# LissajousRevA.net
KiCad netlist of a schematic drawn in EAGLE
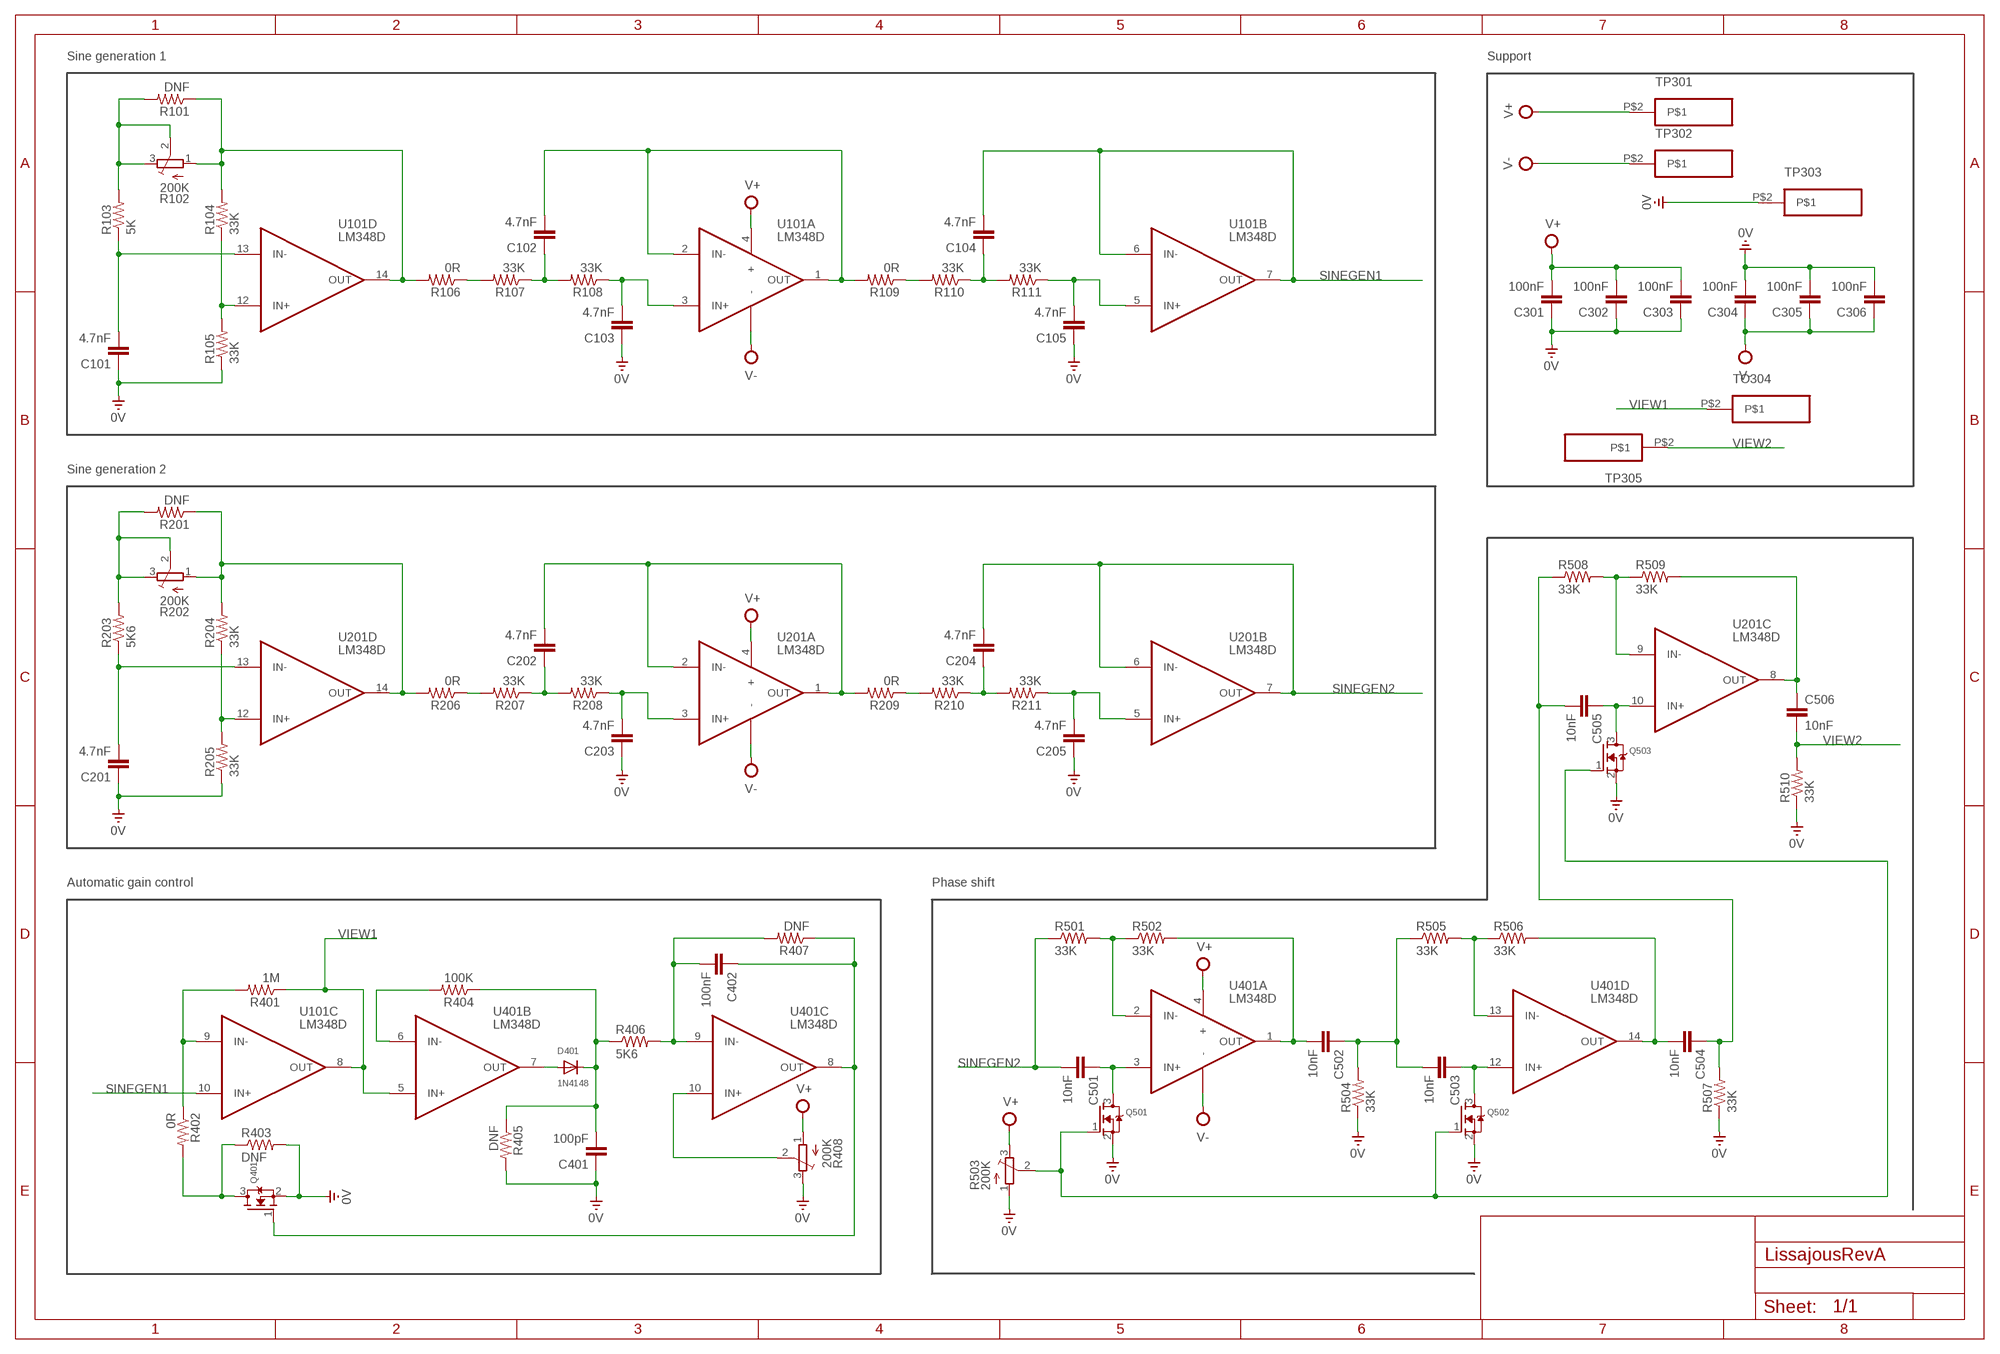
[diagram p0: schematic, sheet 1]

(export (version "E")
  (design (tool "Eeschema 10.0.6"))
  (components
    (comp (ref "C101")
      (value "4.7nF")
      (footprint "eagle-import:0603-CAP")
      (libsource (lib "eagle-import") (part "CAP0603-CAP"))
    )
    (comp (ref "C102")
      (value "4.7nF")
      (footprint "eagle-import:0603-CAP")
      (libsource (lib "eagle-import") (part "CAP0603-CAP"))
    )
    (comp (ref "C103")
      (value "4.7nF")
      (footprint "eagle-import:0603-CAP")
      (libsource (lib "eagle-import") (part "CAP0603-CAP"))
    )
    (comp (ref "C104")
      (value "4.7nF")
      (footprint "eagle-import:0603-CAP")
      (libsource (lib "eagle-import") (part "CAP0603-CAP"))
    )
    (comp (ref "C105")
      (value "4.7nF")
      (footprint "eagle-import:0603-CAP")
      (libsource (lib "eagle-import") (part "CAP0603-CAP"))
    )
    (comp (ref "C201")
      (value "4.7nF")
      (footprint "eagle-import:0603-CAP")
      (libsource (lib "eagle-import") (part "CAP0603-CAP"))
    )
    (comp (ref "C202")
      (value "4.7nF")
      (footprint "eagle-import:0603-CAP")
      (libsource (lib "eagle-import") (part "CAP0603-CAP"))
    )
    (comp (ref "C203")
      (value "4.7nF")
      (footprint "eagle-import:0603-CAP")
      (libsource (lib "eagle-import") (part "CAP0603-CAP"))
    )
    (comp (ref "C204")
      (value "4.7nF")
      (footprint "eagle-import:0603-CAP")
      (libsource (lib "eagle-import") (part "CAP0603-CAP"))
    )
    (comp (ref "C205")
      (value "4.7nF")
      (footprint "eagle-import:0603-CAP")
      (libsource (lib "eagle-import") (part "CAP0603-CAP"))
    )
    (comp (ref "C301")
      (value "100nF")
      (footprint "eagle-import:0603-CAP")
      (libsource (lib "eagle-import") (part "CAP0603-CAP"))
    )
    (comp (ref "C302")
      (value "100nF")
      (footprint "eagle-import:0603-CAP")
      (libsource (lib "eagle-import") (part "CAP0603-CAP"))
    )
    (comp (ref "C303")
      (value "100nF")
      (footprint "eagle-import:0603-CAP")
      (libsource (lib "eagle-import") (part "CAP0603-CAP"))
    )
    (comp (ref "C304")
      (value "100nF")
      (footprint "eagle-import:0603-CAP")
      (libsource (lib "eagle-import") (part "CAP0603-CAP"))
    )
    (comp (ref "C305")
      (value "100nF")
      (footprint "eagle-import:0603-CAP")
      (libsource (lib "eagle-import") (part "CAP0603-CAP"))
    )
    (comp (ref "C306")
      (value "100nF")
      (footprint "eagle-import:0603-CAP")
      (libsource (lib "eagle-import") (part "CAP0603-CAP"))
    )
    (comp (ref "C401")
      (value "100pF")
      (footprint "eagle-import:0603-CAP")
      (libsource (lib "eagle-import") (part "CAP0603-CAP"))
    )
    (comp (ref "C402")
      (value "100nF")
      (footprint "eagle-import:0603-CAP")
      (libsource (lib "eagle-import") (part "CAP0603-CAP"))
    )
    (comp (ref "C501")
      (value "10nF")
      (footprint "eagle-import:0603-CAP")
      (libsource (lib "eagle-import") (part "CAP0603-CAP"))
    )
    (comp (ref "C502")
      (value "10nF")
      (footprint "eagle-import:0603-CAP")
      (libsource (lib "eagle-import") (part "CAP0603-CAP"))
    )
    (comp (ref "C503")
      (value "10nF")
      (footprint "eagle-import:0603-CAP")
      (libsource (lib "eagle-import") (part "CAP0603-CAP"))
    )
    (comp (ref "C504")
      (value "10nF")
      (footprint "eagle-import:0603-CAP")
      (libsource (lib "eagle-import") (part "CAP0603-CAP"))
    )
    (comp (ref "C505")
      (value "10nF")
      (footprint "eagle-import:0603-CAP")
      (libsource (lib "eagle-import") (part "CAP0603-CAP"))
    )
    (comp (ref "C506")
      (value "10nF")
      (footprint "eagle-import:0603-CAP")
      (libsource (lib "eagle-import") (part "CAP0603-CAP"))
    )
    (comp (ref "D401")
      (value "1N4148")
      (footprint "eagle-import:SMADIODE")
      (libsource (lib "eagle-import") (part "DIODESMA"))
    )
    (comp (ref "Q401")
      (value "MOSFET-NREFLOW")
      (footprint "eagle-import:SOT23")
      (libsource (lib "eagle-import") (part "MOSFET-NREFLOW"))
    )
    (comp (ref "Q501")
      (value "MOSFET-NREFLOW")
      (footprint "eagle-import:SOT23")
      (libsource (lib "eagle-import") (part "MOSFET-NREFLOW"))
    )
    (comp (ref "Q502")
      (value "MOSFET-NREFLOW")
      (footprint "eagle-import:SOT23")
      (libsource (lib "eagle-import") (part "MOSFET-NREFLOW"))
    )
    (comp (ref "Q503")
      (value "MOSFET-NREFLOW")
      (footprint "eagle-import:SOT23")
      (libsource (lib "eagle-import") (part "MOSFET-NREFLOW"))
    )
    (comp (ref "R101")
      (value "DNF")
      (footprint "eagle-import:0603-RES")
      (libsource (lib "eagle-import") (part "RESISTOR0603-RES"))
    )
    (comp (ref "R102")
      (value "200K")
      (footprint "eagle-import:TC33X")
      (libsource (lib "eagle-import") (part "TRIMPOTTC33X"))
    )
    (comp (ref "R103")
      (value "5K")
      (footprint "eagle-import:0603-RES")
      (libsource (lib "eagle-import") (part "RESISTOR0603-RES"))
    )
    (comp (ref "R104")
      (value "33K")
      (footprint "eagle-import:0603-RES")
      (libsource (lib "eagle-import") (part "RESISTOR0603-RES"))
    )
    (comp (ref "R105")
      (value "33K")
      (footprint "eagle-import:0603-RES")
      (libsource (lib "eagle-import") (part "RESISTOR0603-RES"))
    )
    (comp (ref "R106")
      (value "0R")
      (footprint "eagle-import:0603-RES")
      (libsource (lib "eagle-import") (part "RESISTOR0603-RES"))
    )
    (comp (ref "R107")
      (value "33K")
      (footprint "eagle-import:0603-RES")
      (libsource (lib "eagle-import") (part "RESISTOR0603-RES"))
    )
    (comp (ref "R108")
      (value "33K")
      (footprint "eagle-import:0603-RES")
      (libsource (lib "eagle-import") (part "RESISTOR0603-RES"))
    )
    (comp (ref "R109")
      (value "0R")
      (footprint "eagle-import:0603-RES")
      (libsource (lib "eagle-import") (part "RESISTOR0603-RES"))
    )
    (comp (ref "R110")
      (value "33K")
      (footprint "eagle-import:0603-RES")
      (libsource (lib "eagle-import") (part "RESISTOR0603-RES"))
    )
    (comp (ref "R111")
      (value "33K")
      (footprint "eagle-import:0603-RES")
      (libsource (lib "eagle-import") (part "RESISTOR0603-RES"))
    )
    (comp (ref "R201")
      (value "DNF")
      (footprint "eagle-import:0603-RES")
      (libsource (lib "eagle-import") (part "RESISTOR0603-RES"))
    )
    (comp (ref "R202")
      (value "200K")
      (footprint "eagle-import:TC33X")
      (libsource (lib "eagle-import") (part "TRIMPOTTC33X"))
    )
    (comp (ref "R203")
      (value "5K6")
      (footprint "eagle-import:0603-RES")
      (libsource (lib "eagle-import") (part "RESISTOR0603-RES"))
    )
    (comp (ref "R204")
      (value "33K")
      (footprint "eagle-import:0603-RES")
      (libsource (lib "eagle-import") (part "RESISTOR0603-RES"))
    )
    (comp (ref "R205")
      (value "33K")
      (footprint "eagle-import:0603-RES")
      (libsource (lib "eagle-import") (part "RESISTOR0603-RES"))
    )
    (comp (ref "R206")
      (value "0R")
      (footprint "eagle-import:0603-RES")
      (libsource (lib "eagle-import") (part "RESISTOR0603-RES"))
    )
    (comp (ref "R207")
      (value "33K")
      (footprint "eagle-import:0603-RES")
      (libsource (lib "eagle-import") (part "RESISTOR0603-RES"))
    )
    (comp (ref "R208")
      (value "33K")
      (footprint "eagle-import:0603-RES")
      (libsource (lib "eagle-import") (part "RESISTOR0603-RES"))
    )
    (comp (ref "R209")
      (value "0R")
      (footprint "eagle-import:0603-RES")
      (libsource (lib "eagle-import") (part "RESISTOR0603-RES"))
    )
    (comp (ref "R210")
      (value "33K")
      (footprint "eagle-import:0603-RES")
      (libsource (lib "eagle-import") (part "RESISTOR0603-RES"))
    )
    (comp (ref "R211")
      (value "33K")
      (footprint "eagle-import:0603-RES")
      (libsource (lib "eagle-import") (part "RESISTOR0603-RES"))
    )
    (comp (ref "R401")
      (value "1M")
      (footprint "eagle-import:0603-RES")
      (libsource (lib "eagle-import") (part "RESISTOR0603-RES"))
    )
    (comp (ref "R402")
      (value "0R")
      (footprint "eagle-import:0603-RES")
      (libsource (lib "eagle-import") (part "RESISTOR0603-RES"))
    )
    (comp (ref "R403")
      (value "DNF")
      (footprint "eagle-import:0603-RES")
      (libsource (lib "eagle-import") (part "RESISTOR0603-RES"))
    )
    (comp (ref "R404")
      (value "100K")
      (footprint "eagle-import:0603-RES")
      (libsource (lib "eagle-import") (part "RESISTOR0603-RES"))
    )
    (comp (ref "R405")
      (value "DNF")
      (footprint "eagle-import:0603-RES")
      (libsource (lib "eagle-import") (part "RESISTOR0603-RES"))
    )
    (comp (ref "R406")
      (value "5K6")
      (footprint "eagle-import:0603-RES")
      (libsource (lib "eagle-import") (part "RESISTOR0603-RES"))
    )
    (comp (ref "R407")
      (value "DNF")
      (footprint "eagle-import:0603-RES")
      (libsource (lib "eagle-import") (part "RESISTOR0603-RES"))
    )
    (comp (ref "R408")
      (value "200K")
      (footprint "eagle-import:TC33X")
      (libsource (lib "eagle-import") (part "TRIMPOTTC33X"))
    )
    (comp (ref "R501")
      (value "33K")
      (footprint "eagle-import:0603-RES")
      (libsource (lib "eagle-import") (part "RESISTOR0603-RES"))
    )
    (comp (ref "R502")
      (value "33K")
      (footprint "eagle-import:0603-RES")
      (libsource (lib "eagle-import") (part "RESISTOR0603-RES"))
    )
    (comp (ref "R503")
      (value "200K")
      (footprint "eagle-import:TC33X")
      (libsource (lib "eagle-import") (part "TRIMPOTTC33X"))
    )
    (comp (ref "R504")
      (value "33K")
      (footprint "eagle-import:0603-RES")
      (libsource (lib "eagle-import") (part "RESISTOR0603-RES"))
    )
    (comp (ref "R505")
      (value "33K")
      (footprint "eagle-import:0603-RES")
      (libsource (lib "eagle-import") (part "RESISTOR0603-RES"))
    )
    (comp (ref "R506")
      (value "33K")
      (footprint "eagle-import:0603-RES")
      (libsource (lib "eagle-import") (part "RESISTOR0603-RES"))
    )
    (comp (ref "R507")
      (value "33K")
      (footprint "eagle-import:0603-RES")
      (libsource (lib "eagle-import") (part "RESISTOR0603-RES"))
    )
    (comp (ref "R508")
      (value "33K")
      (footprint "eagle-import:0603-RES")
      (libsource (lib "eagle-import") (part "RESISTOR0603-RES"))
    )
    (comp (ref "R509")
      (value "33K")
      (footprint "eagle-import:0603-RES")
      (libsource (lib "eagle-import") (part "RESISTOR0603-RES"))
    )
    (comp (ref "R510")
      (value "33K")
      (footprint "eagle-import:0603-RES")
      (libsource (lib "eagle-import") (part "RESISTOR0603-RES"))
    )
    (comp (ref "TO304")
      (value "PAD")
      (footprint "eagle-import:PAD")
      (libsource (lib "eagle-import") (part "PAD"))
    )
    (comp (ref "TP301")
      (value "PAD")
      (footprint "eagle-import:PAD")
      (libsource (lib "eagle-import") (part "PAD"))
    )
    (comp (ref "TP302")
      (value "PAD")
      (footprint "eagle-import:PAD")
      (libsource (lib "eagle-import") (part "PAD"))
    )
    (comp (ref "TP303")
      (value "PAD")
      (footprint "eagle-import:PAD")
      (libsource (lib "eagle-import") (part "PAD"))
    )
    (comp (ref "TP305")
      (value "PAD")
      (footprint "eagle-import:PAD")
      (libsource (lib "eagle-import") (part "PAD"))
    )
    (comp (ref "U101")
      (value "LM348D")
      (footprint "eagle-import:SOIC127P600X175-14N")
      (libsource (lib "eagle-import") (part "LM348D"))
    )
    (comp (ref "U201")
      (value "LM348D")
      (footprint "eagle-import:SOIC127P600X175-14N")
      (libsource (lib "eagle-import") (part "LM348D"))
    )
    (comp (ref "U401")
      (value "LM348D")
      (footprint "eagle-import:SOIC127P600X175-14N")
      (libsource (lib "eagle-import") (part "LM348D"))
    )
  )
  (nets
    (net (code "1") (name "/SINEGEN1") (class "Default")
      (node (ref "C104") (pin "2") (pinfunction "2_2") (pintype "passive"))
      (node (ref "U101") (pin "10") (pinfunction "IN+_10") (pintype "output"))
      (node (ref "U101") (pin "6") (pinfunction "IN-_6") (pintype "output"))
      (node (ref "U101") (pin "7") (pinfunction "OUT_7") (pintype "output"))
    )
    (net (code "2") (name "/SINEGEN2") (class "Default")
      (node (ref "C204") (pin "2") (pinfunction "2_2") (pintype "passive"))
      (node (ref "C501") (pin "2") (pinfunction "2_2") (pintype "passive"))
      (node (ref "R501") (pin "1") (pinfunction "1_1") (pintype "passive"))
      (node (ref "U201") (pin "6") (pinfunction "IN-_6") (pintype "output"))
      (node (ref "U201") (pin "7") (pinfunction "OUT_7") (pintype "output"))
    )
    (net (code "3") (name "/VIEW1") (class "Default")
      (node (ref "R401") (pin "1") (pinfunction "1_1") (pintype "passive"))
      (node (ref "TO304") (pin "P$2") (pinfunction "P$1_P$2") (pintype "bidirectional"))
      (node (ref "U101") (pin "8") (pinfunction "OUT_8") (pintype "output"))
      (node (ref "U401") (pin "5") (pinfunction "IN+_5") (pintype "output"))
    )
    (net (code "4") (name "/VIEW2") (class "Default")
      (node (ref "C506") (pin "2") (pinfunction "2_2") (pintype "passive"))
      (node (ref "R510") (pin "2") (pinfunction "2_2") (pintype "passive"))
      (node (ref "TP305") (pin "P$2") (pinfunction "P$1_P$2") (pintype "bidirectional"))
    )
    (net (code "5") (name "0V") (class "Default")
      (node (ref "C101") (pin "1") (pinfunction "1_1") (pintype "passive"))
      (node (ref "C103") (pin "1") (pinfunction "1_1") (pintype "passive"))
      (node (ref "C105") (pin "1") (pinfunction "1_1") (pintype "passive"))
      (node (ref "C201") (pin "1") (pinfunction "1_1") (pintype "passive"))
      (node (ref "C203") (pin "1") (pinfunction "1_1") (pintype "passive"))
      (node (ref "C205") (pin "1") (pinfunction "1_1") (pintype "passive"))
      (node (ref "C301") (pin "1") (pinfunction "1_1") (pintype "passive"))
      (node (ref "C302") (pin "1") (pinfunction "1_1") (pintype "passive"))
      (node (ref "C303") (pin "1") (pinfunction "1_1") (pintype "passive"))
      (node (ref "C304") (pin "2") (pinfunction "2_2") (pintype "passive"))
      (node (ref "C305") (pin "2") (pinfunction "2_2") (pintype "passive"))
      (node (ref "C306") (pin "2") (pinfunction "2_2") (pintype "passive"))
      (node (ref "C401") (pin "1") (pinfunction "1_1") (pintype "passive"))
      (node (ref "Q401") (pin "2") (pinfunction "S_2") (pintype "bidirectional"))
      (node (ref "Q501") (pin "2") (pinfunction "S_2") (pintype "bidirectional"))
      (node (ref "Q502") (pin "2") (pinfunction "S_2") (pintype "bidirectional"))
      (node (ref "Q503") (pin "2") (pinfunction "S_2") (pintype "bidirectional"))
      (node (ref "R105") (pin "1") (pinfunction "1_1") (pintype "passive"))
      (node (ref "R205") (pin "1") (pinfunction "1_1") (pintype "passive"))
      (node (ref "R403") (pin "2") (pinfunction "2_2") (pintype "passive"))
      (node (ref "R405") (pin "2") (pinfunction "2_2") (pintype "passive"))
      (node (ref "R408") (pin "3") (pinfunction "E_3") (pintype "passive"))
      (node (ref "R503") (pin "1") (pinfunction "A_1") (pintype "passive"))
      (node (ref "R504") (pin "1") (pinfunction "1_1") (pintype "passive"))
      (node (ref "R507") (pin "1") (pinfunction "1_1") (pintype "passive"))
      (node (ref "R510") (pin "1") (pinfunction "1_1") (pintype "passive"))
      (node (ref "TP303") (pin "P$2") (pinfunction "P$1_P$2") (pintype "bidirectional"))
    )
    (net (code "6") (name "Net-(C102-Pad1)") (class "Default")
      (node (ref "C102") (pin "1") (pinfunction "1_1") (pintype "passive"))
      (node (ref "R107") (pin "1") (pinfunction "1_1") (pintype "passive"))
      (node (ref "R108") (pin "2") (pinfunction "2_2") (pintype "passive"))
    )
    (net (code "7") (name "Net-(C104-Pad1)") (class "Default")
      (node (ref "C104") (pin "1") (pinfunction "1_1") (pintype "passive"))
      (node (ref "R110") (pin "1") (pinfunction "1_1") (pintype "passive"))
      (node (ref "R111") (pin "2") (pinfunction "2_2") (pintype "passive"))
    )
    (net (code "8") (name "Net-(C202-Pad1)") (class "Default")
      (node (ref "C202") (pin "1") (pinfunction "1_1") (pintype "passive"))
      (node (ref "R207") (pin "1") (pinfunction "1_1") (pintype "passive"))
      (node (ref "R208") (pin "2") (pinfunction "2_2") (pintype "passive"))
    )
    (net (code "9") (name "Net-(C204-Pad1)") (class "Default")
      (node (ref "C204") (pin "1") (pinfunction "1_1") (pintype "passive"))
      (node (ref "R210") (pin "1") (pinfunction "1_1") (pintype "passive"))
      (node (ref "R211") (pin "2") (pinfunction "2_2") (pintype "passive"))
    )
    (net (code "10") (name "Net-(C401-Pad2)") (class "Default")
      (node (ref "C401") (pin "2") (pinfunction "2_2") (pintype "passive"))
      (node (ref "D401") (pin "C") (pinfunction "C_C") (pintype "passive"))
      (node (ref "R404") (pin "1") (pinfunction "1_1") (pintype "passive"))
      (node (ref "R405") (pin "1") (pinfunction "1_1") (pintype "passive"))
      (node (ref "R406") (pin "1") (pinfunction "1_1") (pintype "passive"))
    )
    (net (code "11") (name "Net-(C502-Pad1)") (class "Default")
      (node (ref "C502") (pin "1") (pinfunction "1_1") (pintype "passive"))
      (node (ref "C503") (pin "2") (pinfunction "2_2") (pintype "passive"))
      (node (ref "R504") (pin "2") (pinfunction "2_2") (pintype "passive"))
      (node (ref "R505") (pin "1") (pinfunction "1_1") (pintype "passive"))
    )
    (net (code "12") (name "Net-(C504-Pad1)") (class "Default")
      (node (ref "C504") (pin "1") (pinfunction "1_1") (pintype "passive"))
      (node (ref "C505") (pin "2") (pinfunction "2_2") (pintype "passive"))
      (node (ref "R507") (pin "2") (pinfunction "2_2") (pintype "passive"))
      (node (ref "R508") (pin "1") (pinfunction "1_1") (pintype "passive"))
    )
    (net (code "13") (name "Net-(Q401-D)") (class "Default")
      (node (ref "Q401") (pin "3") (pinfunction "D_3") (pintype "bidirectional"))
      (node (ref "R402") (pin "2") (pinfunction "2_2") (pintype "passive"))
      (node (ref "R403") (pin "1") (pinfunction "1_1") (pintype "passive"))
    )
    (net (code "14") (name "Net-(Q401-G)") (class "Default")
      (node (ref "C402") (pin "1") (pinfunction "1_1") (pintype "passive"))
      (node (ref "Q401") (pin "1") (pinfunction "G_1") (pintype "bidirectional"))
      (node (ref "R407") (pin "1") (pinfunction "1_1") (pintype "passive"))
      (node (ref "U401") (pin "8") (pinfunction "OUT_8") (pintype "output"))
    )
    (net (code "15") (name "Net-(Q501-D)") (class "Default")
      (node (ref "C501") (pin "1") (pinfunction "1_1") (pintype "passive"))
      (node (ref "Q501") (pin "3") (pinfunction "D_3") (pintype "bidirectional"))
      (node (ref "U401") (pin "3") (pinfunction "IN+_3") (pintype "output"))
    )
    (net (code "16") (name "Net-(Q501-G)") (class "Default")
      (node (ref "Q501") (pin "1") (pinfunction "G_1") (pintype "bidirectional"))
      (node (ref "Q502") (pin "1") (pinfunction "G_1") (pintype "bidirectional"))
      (node (ref "Q503") (pin "1") (pinfunction "G_1") (pintype "bidirectional"))
      (node (ref "R503") (pin "2") (pinfunction "S_2") (pintype "passive"))
    )
    (net (code "17") (name "Net-(Q502-D)") (class "Default")
      (node (ref "C503") (pin "1") (pinfunction "1_1") (pintype "passive"))
      (node (ref "Q502") (pin "3") (pinfunction "D_3") (pintype "bidirectional"))
      (node (ref "U401") (pin "12") (pinfunction "IN+_12") (pintype "output"))
    )
    (net (code "18") (name "Net-(Q503-D)") (class "Default")
      (node (ref "C505") (pin "1") (pinfunction "1_1") (pintype "passive"))
      (node (ref "Q503") (pin "3") (pinfunction "D_3") (pintype "bidirectional"))
      (node (ref "U201") (pin "10") (pinfunction "IN+_10") (pintype "output"))
    )
    (net (code "19") (name "Net-(R102-A)") (class "Default")
      (node (ref "R101") (pin "1") (pinfunction "1_1") (pintype "passive"))
      (node (ref "R102") (pin "1") (pinfunction "A_1") (pintype "passive"))
      (node (ref "R104") (pin "2") (pinfunction "2_2") (pintype "passive"))
      (node (ref "R106") (pin "2") (pinfunction "2_2") (pintype "passive"))
      (node (ref "U101") (pin "14") (pinfunction "OUT_14") (pintype "output"))
    )
    (net (code "20") (name "Net-(R102-E)") (class "Default")
      (node (ref "R101") (pin "2") (pinfunction "2_2") (pintype "passive"))
      (node (ref "R102") (pin "2") (pinfunction "S_2") (pintype "passive"))
      (node (ref "R102") (pin "3") (pinfunction "E_3") (pintype "passive"))
      (node (ref "R103") (pin "2") (pinfunction "2_2") (pintype "passive"))
    )
    (net (code "21") (name "Net-(R106-Pad1)") (class "Default")
      (node (ref "R106") (pin "1") (pinfunction "1_1") (pintype "passive"))
      (node (ref "R107") (pin "2") (pinfunction "2_2") (pintype "passive"))
    )
    (net (code "22") (name "Net-(R109-Pad1)") (class "Default")
      (node (ref "R109") (pin "1") (pinfunction "1_1") (pintype "passive"))
      (node (ref "R110") (pin "2") (pinfunction "2_2") (pintype "passive"))
    )
    (net (code "23") (name "Net-(R202-A)") (class "Default")
      (node (ref "R201") (pin "1") (pinfunction "1_1") (pintype "passive"))
      (node (ref "R202") (pin "1") (pinfunction "A_1") (pintype "passive"))
      (node (ref "R204") (pin "2") (pinfunction "2_2") (pintype "passive"))
      (node (ref "R206") (pin "2") (pinfunction "2_2") (pintype "passive"))
      (node (ref "U201") (pin "14") (pinfunction "OUT_14") (pintype "output"))
    )
    (net (code "24") (name "Net-(R202-E)") (class "Default")
      (node (ref "R201") (pin "2") (pinfunction "2_2") (pintype "passive"))
      (node (ref "R202") (pin "2") (pinfunction "S_2") (pintype "passive"))
      (node (ref "R202") (pin "3") (pinfunction "E_3") (pintype "passive"))
      (node (ref "R203") (pin "2") (pinfunction "2_2") (pintype "passive"))
    )
    (net (code "25") (name "Net-(R206-Pad1)") (class "Default")
      (node (ref "R206") (pin "1") (pinfunction "1_1") (pintype "passive"))
      (node (ref "R207") (pin "2") (pinfunction "2_2") (pintype "passive"))
    )
    (net (code "26") (name "Net-(R209-Pad1)") (class "Default")
      (node (ref "R209") (pin "1") (pinfunction "1_1") (pintype "passive"))
      (node (ref "R210") (pin "2") (pinfunction "2_2") (pintype "passive"))
    )
    (net (code "27") (name "Net-(R408-S)") (class "Default")
      (node (ref "R408") (pin "2") (pinfunction "S_2") (pintype "passive"))
      (node (ref "U401") (pin "10") (pinfunction "IN+_10") (pintype "output"))
    )
    (net (code "28") (name "Net-(U101A-IN+)") (class "Default")
      (node (ref "C103") (pin "2") (pinfunction "2_2") (pintype "passive"))
      (node (ref "R108") (pin "1") (pinfunction "1_1") (pintype "passive"))
      (node (ref "U101") (pin "3") (pinfunction "IN+_3") (pintype "output"))
    )
    (net (code "29") (name "Net-(U101A-IN-)") (class "Default")
      (node (ref "C102") (pin "2") (pinfunction "2_2") (pintype "passive"))
      (node (ref "R109") (pin "2") (pinfunction "2_2") (pintype "passive"))
      (node (ref "U101") (pin "1") (pinfunction "OUT_1") (pintype "output"))
      (node (ref "U101") (pin "2") (pinfunction "IN-_2") (pintype "output"))
    )
    (net (code "30") (name "Net-(U101B-IN+)") (class "Default")
      (node (ref "C105") (pin "2") (pinfunction "2_2") (pintype "passive"))
      (node (ref "R111") (pin "1") (pinfunction "1_1") (pintype "passive"))
      (node (ref "U101") (pin "5") (pinfunction "IN+_5") (pintype "output"))
    )
    (net (code "31") (name "Net-(U101C-IN-)") (class "Default")
      (node (ref "R401") (pin "2") (pinfunction "2_2") (pintype "passive"))
      (node (ref "R402") (pin "1") (pinfunction "1_1") (pintype "passive"))
      (node (ref "U101") (pin "9") (pinfunction "IN-_9") (pintype "output"))
    )
    (net (code "32") (name "Net-(U101D-IN+)") (class "Default")
      (node (ref "R104") (pin "1") (pinfunction "1_1") (pintype "passive"))
      (node (ref "R105") (pin "2") (pinfunction "2_2") (pintype "passive"))
      (node (ref "U101") (pin "12") (pinfunction "IN+_12") (pintype "output"))
    )
    (net (code "33") (name "Net-(U101D-IN-)") (class "Default")
      (node (ref "C101") (pin "2") (pinfunction "2_2") (pintype "passive"))
      (node (ref "R103") (pin "1") (pinfunction "1_1") (pintype "passive"))
      (node (ref "U101") (pin "13") (pinfunction "IN-_13") (pintype "output"))
    )
    (net (code "34") (name "Net-(U201A-IN+)") (class "Default")
      (node (ref "C203") (pin "2") (pinfunction "2_2") (pintype "passive"))
      (node (ref "R208") (pin "1") (pinfunction "1_1") (pintype "passive"))
      (node (ref "U201") (pin "3") (pinfunction "IN+_3") (pintype "output"))
    )
    (net (code "35") (name "Net-(U201A-IN-)") (class "Default")
      (node (ref "C202") (pin "2") (pinfunction "2_2") (pintype "passive"))
      (node (ref "R209") (pin "2") (pinfunction "2_2") (pintype "passive"))
      (node (ref "U201") (pin "1") (pinfunction "OUT_1") (pintype "output"))
      (node (ref "U201") (pin "2") (pinfunction "IN-_2") (pintype "output"))
    )
    (net (code "36") (name "Net-(U201B-IN+)") (class "Default")
      (node (ref "C205") (pin "2") (pinfunction "2_2") (pintype "passive"))
      (node (ref "R211") (pin "1") (pinfunction "1_1") (pintype "passive"))
      (node (ref "U201") (pin "5") (pinfunction "IN+_5") (pintype "output"))
    )
    (net (code "37") (name "Net-(U201C-IN-)") (class "Default")
      (node (ref "R508") (pin "2") (pinfunction "2_2") (pintype "passive"))
      (node (ref "R509") (pin "1") (pinfunction "1_1") (pintype "passive"))
      (node (ref "U201") (pin "9") (pinfunction "IN-_9") (pintype "output"))
    )
    (net (code "38") (name "Net-(U201C-OUT)") (class "Default")
      (node (ref "C506") (pin "1") (pinfunction "1_1") (pintype "passive"))
      (node (ref "R509") (pin "2") (pinfunction "2_2") (pintype "passive"))
      (node (ref "U201") (pin "8") (pinfunction "OUT_8") (pintype "output"))
    )
    (net (code "39") (name "Net-(U201D-IN+)") (class "Default")
      (node (ref "R204") (pin "1") (pinfunction "1_1") (pintype "passive"))
      (node (ref "R205") (pin "2") (pinfunction "2_2") (pintype "passive"))
      (node (ref "U201") (pin "12") (pinfunction "IN+_12") (pintype "output"))
    )
    (net (code "40") (name "Net-(U201D-IN-)") (class "Default")
      (node (ref "C201") (pin "2") (pinfunction "2_2") (pintype "passive"))
      (node (ref "R203") (pin "1") (pinfunction "1_1") (pintype "passive"))
      (node (ref "U201") (pin "13") (pinfunction "IN-_13") (pintype "output"))
    )
    (net (code "41") (name "Net-(U401A-IN-)") (class "Default")
      (node (ref "R501") (pin "2") (pinfunction "2_2") (pintype "passive"))
      (node (ref "R502") (pin "1") (pinfunction "1_1") (pintype "passive"))
      (node (ref "U401") (pin "2") (pinfunction "IN-_2") (pintype "output"))
    )
    (net (code "42") (name "Net-(U401A-OUT)") (class "Default")
      (node (ref "C502") (pin "2") (pinfunction "2_2") (pintype "passive"))
      (node (ref "R502") (pin "2") (pinfunction "2_2") (pintype "passive"))
      (node (ref "U401") (pin "1") (pinfunction "OUT_1") (pintype "output"))
    )
    (net (code "43") (name "Net-(U401B-IN-)") (class "Default")
      (node (ref "R404") (pin "2") (pinfunction "2_2") (pintype "passive"))
      (node (ref "U401") (pin "6") (pinfunction "IN-_6") (pintype "output"))
    )
    (net (code "44") (name "Net-(U401B-OUT)") (class "Default")
      (node (ref "D401") (pin "A") (pinfunction "A_A") (pintype "passive"))
      (node (ref "U401") (pin "7") (pinfunction "OUT_7") (pintype "output"))
    )
    (net (code "45") (name "Net-(U401C-IN-)") (class "Default")
      (node (ref "C402") (pin "2") (pinfunction "2_2") (pintype "passive"))
      (node (ref "R406") (pin "2") (pinfunction "2_2") (pintype "passive"))
      (node (ref "R407") (pin "2") (pinfunction "2_2") (pintype "passive"))
      (node (ref "U401") (pin "9") (pinfunction "IN-_9") (pintype "output"))
    )
    (net (code "46") (name "Net-(U401D-IN-)") (class "Default")
      (node (ref "R505") (pin "2") (pinfunction "2_2") (pintype "passive"))
      (node (ref "R506") (pin "1") (pinfunction "1_1") (pintype "passive"))
      (node (ref "U401") (pin "13") (pinfunction "IN-_13") (pintype "output"))
    )
    (net (code "47") (name "Net-(U401D-OUT)") (class "Default")
      (node (ref "C504") (pin "2") (pinfunction "2_2") (pintype "passive"))
      (node (ref "R506") (pin "2") (pinfunction "2_2") (pintype "passive"))
      (node (ref "U401") (pin "14") (pinfunction "OUT_14") (pintype "output"))
    )
    (net (code "48") (name "V+") (class "Default")
      (node (ref "C301") (pin "2") (pinfunction "2_2") (pintype "passive"))
      (node (ref "C302") (pin "2") (pinfunction "2_2") (pintype "passive"))
      (node (ref "C303") (pin "2") (pinfunction "2_2") (pintype "passive"))
      (node (ref "R408") (pin "1") (pinfunction "A_1") (pintype "passive"))
      (node (ref "R503") (pin "3") (pinfunction "E_3") (pintype "passive"))
      (node (ref "TP301") (pin "P$2") (pinfunction "P$1_P$2") (pintype "bidirectional"))
      (node (ref "U101") (pin "4") (pinfunction "+_4") (pintype "output"))
      (node (ref "U201") (pin "4") (pinfunction "+_4") (pintype "output"))
      (node (ref "U401") (pin "4") (pinfunction "+_4") (pintype "output"))
    )
    (net (code "49") (name "V-") (class "Default")
      (node (ref "C304") (pin "1") (pinfunction "1_1") (pintype "passive"))
      (node (ref "C305") (pin "1") (pinfunction "1_1") (pintype "passive"))
      (node (ref "C306") (pin "1") (pinfunction "1_1") (pintype "passive"))
      (node (ref "TP302") (pin "P$2") (pinfunction "P$1_P$2") (pintype "bidirectional"))
      (node (ref "U101") (pin "11") (pinfunction "-_11") (pintype "output"))
      (node (ref "U201") (pin "11") (pinfunction "-_11") (pintype "output"))
      (node (ref "U401") (pin "11") (pinfunction "-_11") (pintype "output"))
    )
  )
)
